# Utable_epaper_32seg_rev2.net
KiCad netlist of a schematic drawn in EAGLE
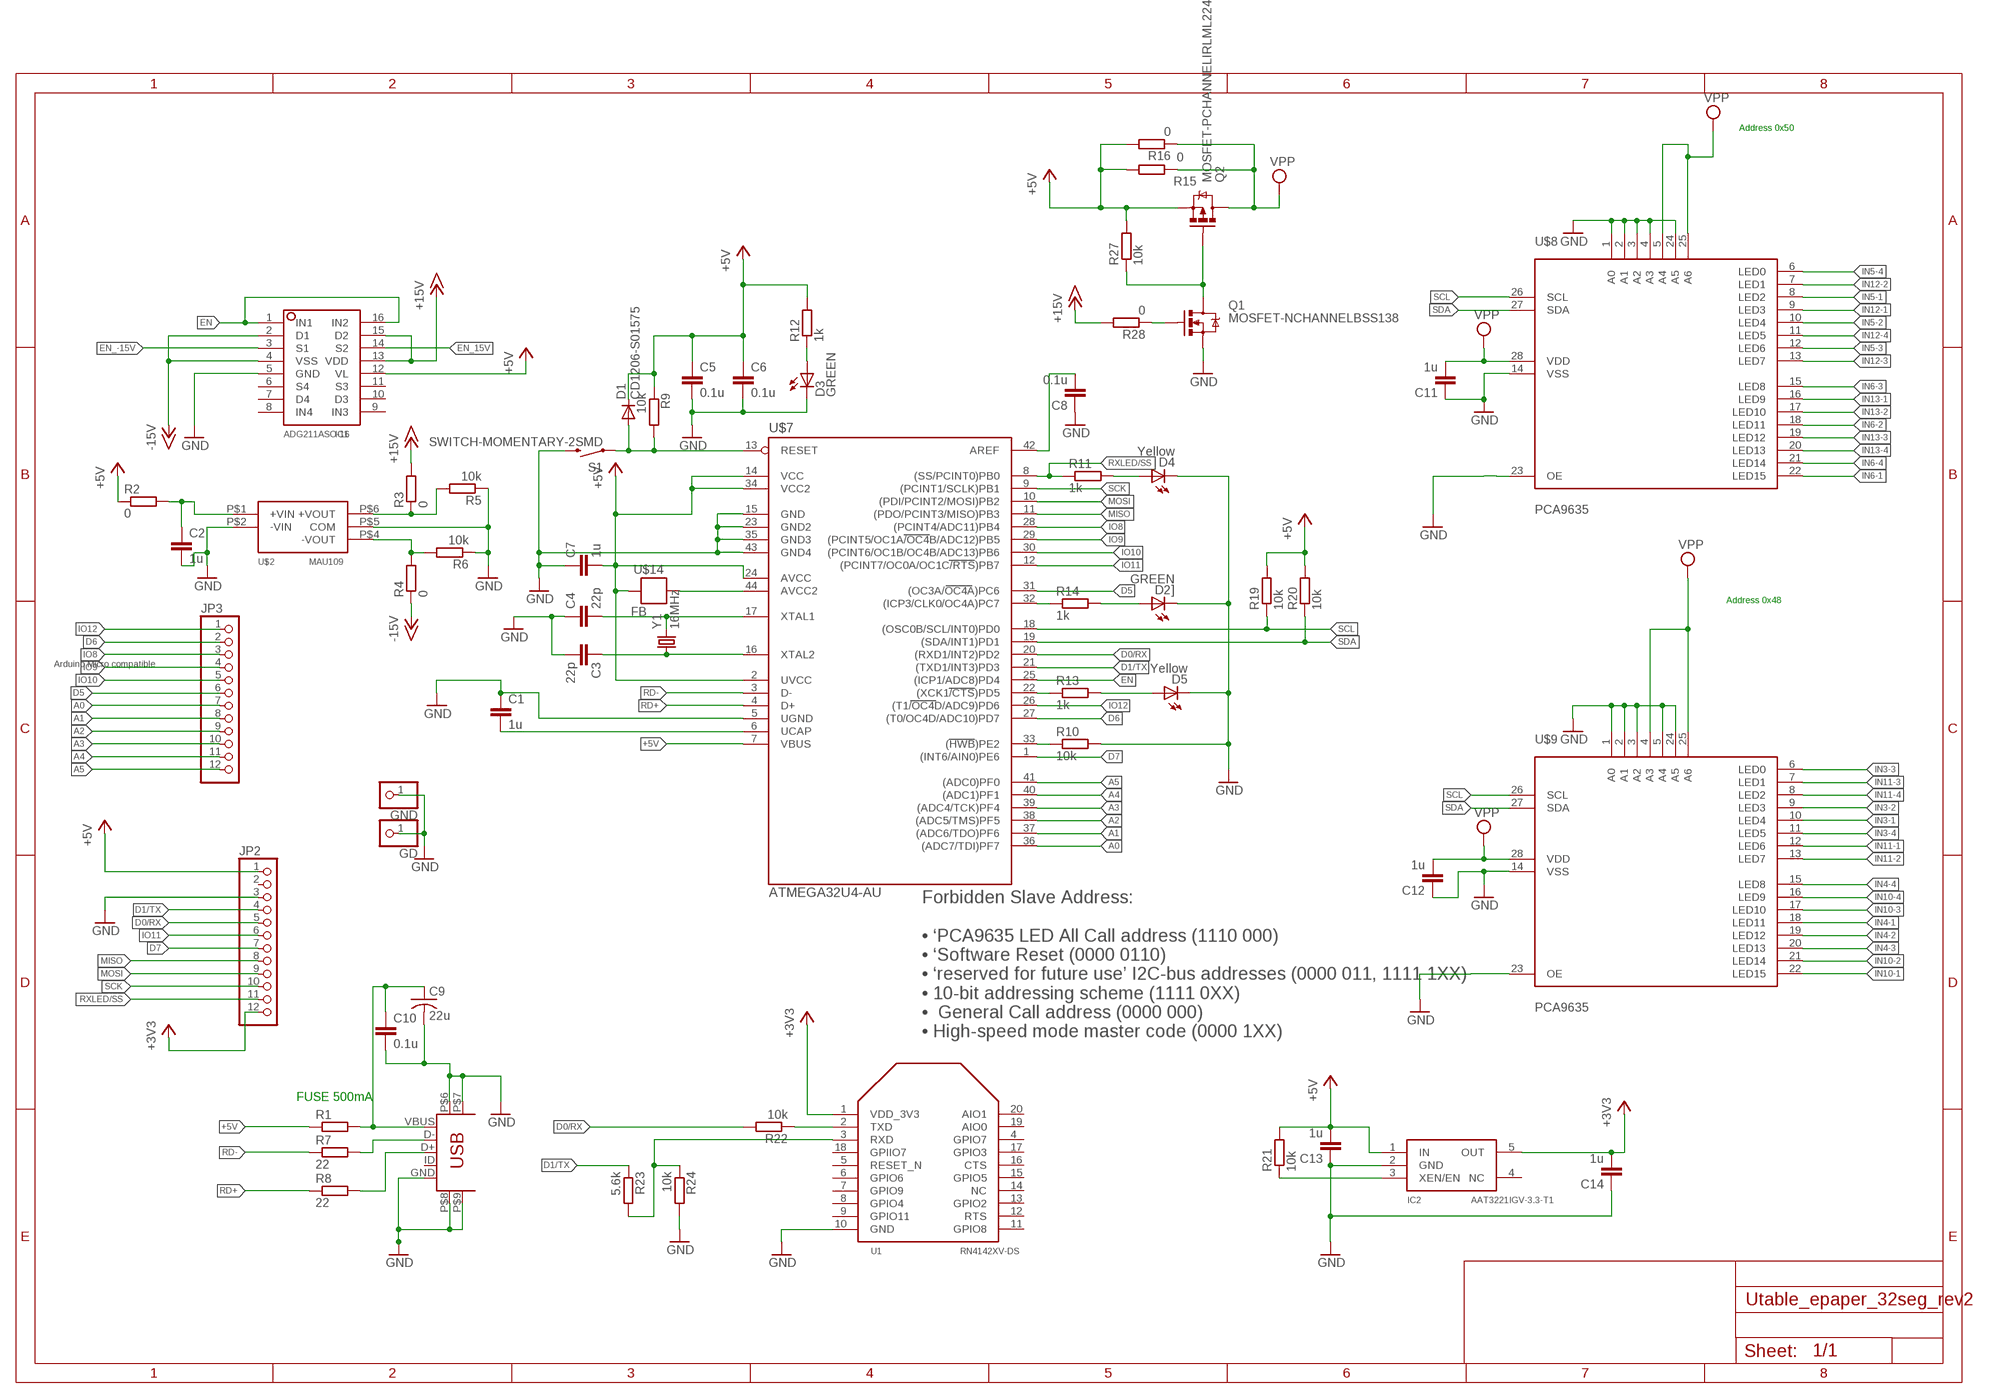
[diagram p0: schematic, sheet 1, part 1 of 2]
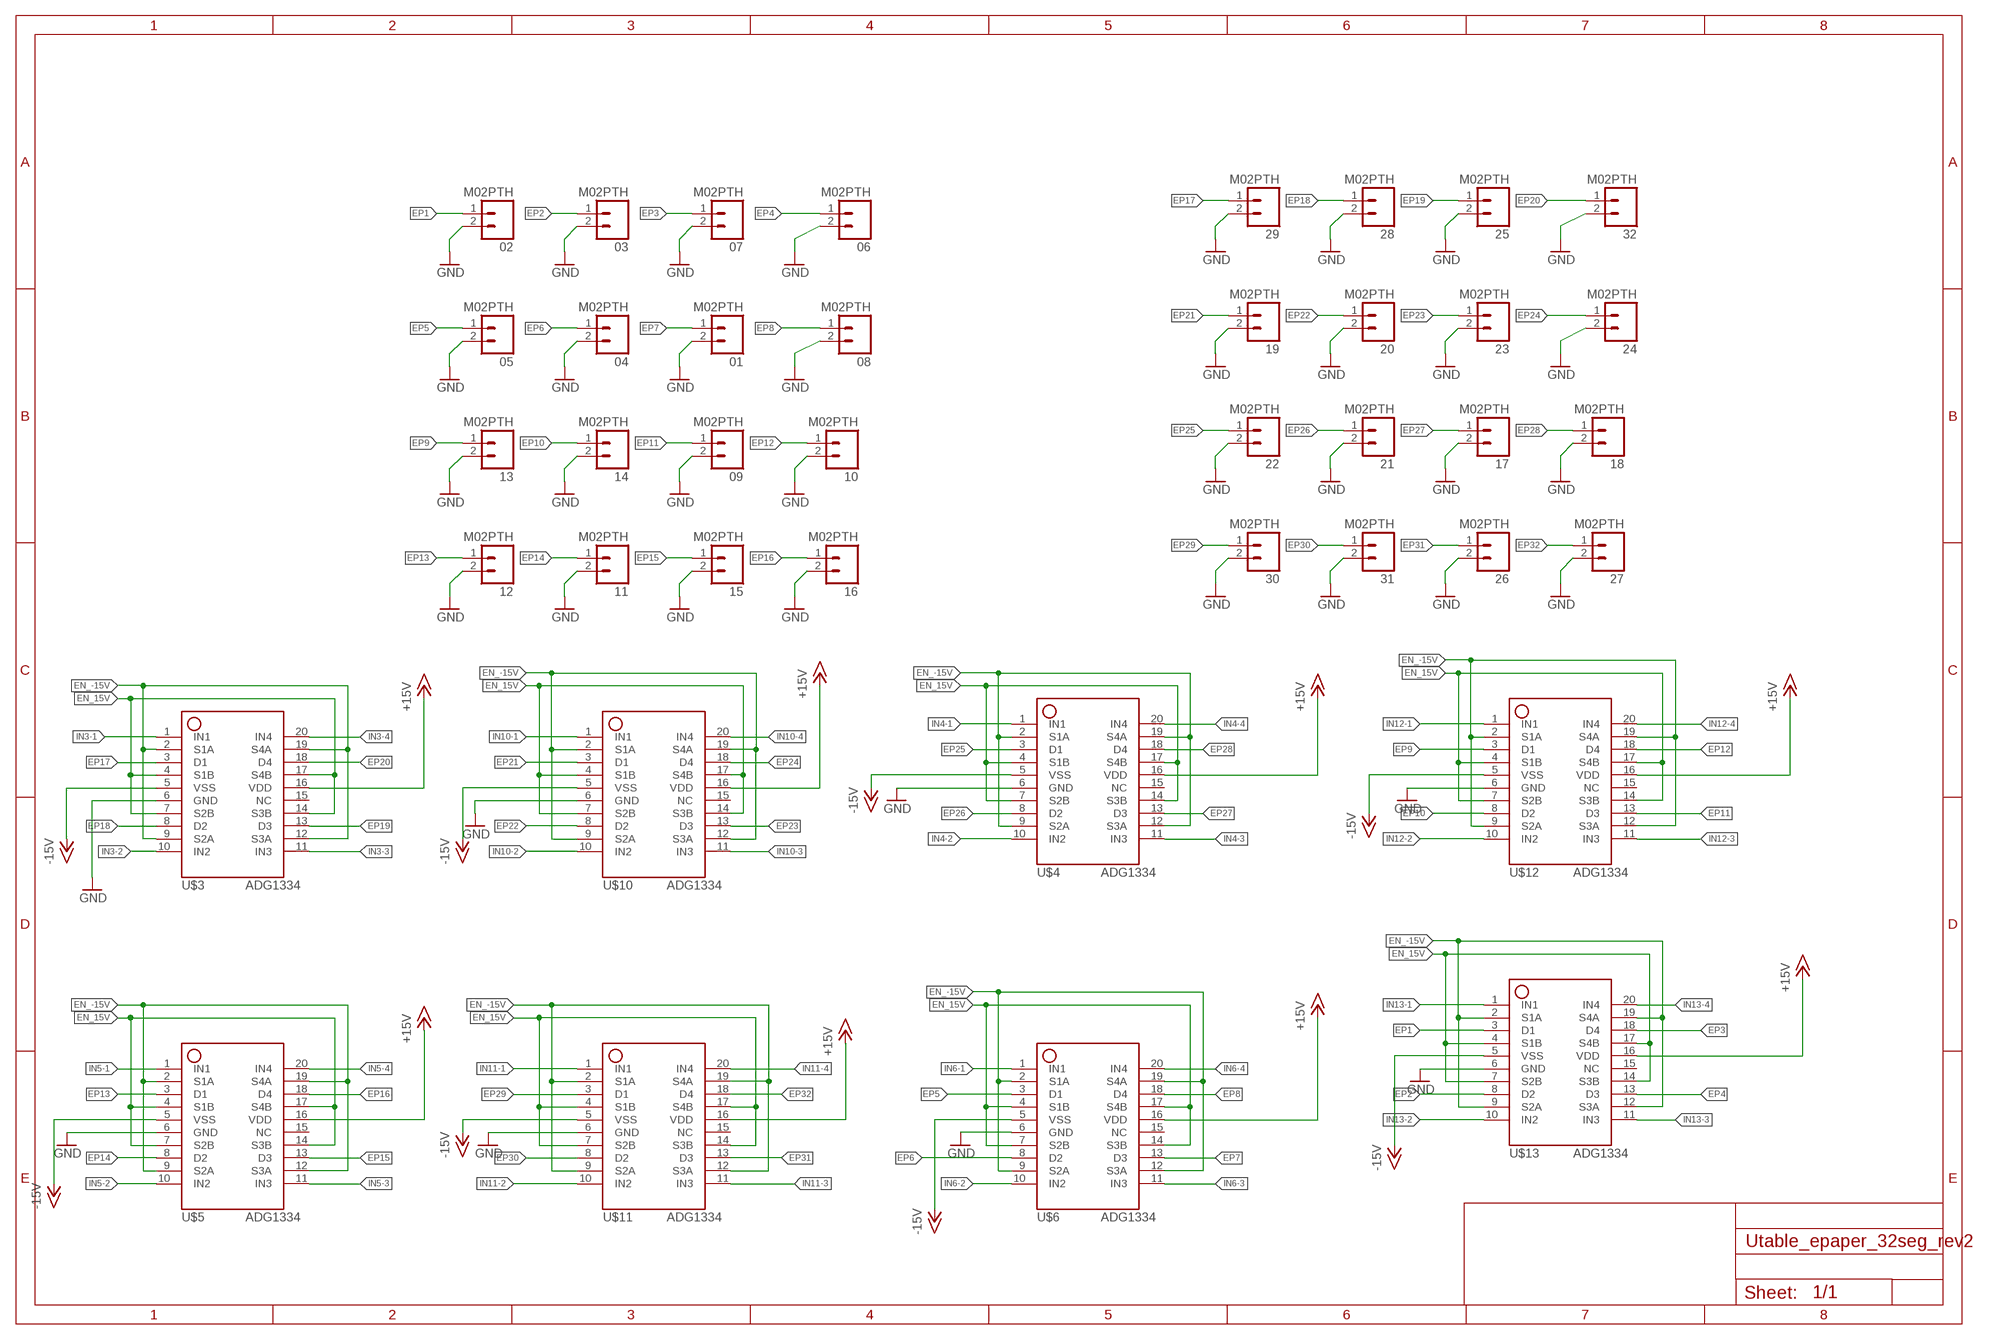
[diagram p1: schematic, sheet 1, part 2 of 2]

(export (version "E")
  (design (tool "Eeschema 10.0.6"))
  (components
    (comp (ref "01")
      (value "M02PTH")
      (footprint "eagle-import:1X02")
      (libsource (lib "eagle-import") (part "M02PTH"))
    )
    (comp (ref "02")
      (value "M02PTH")
      (footprint "eagle-import:1X02")
      (libsource (lib "eagle-import") (part "M02PTH"))
    )
    (comp (ref "03")
      (value "M02PTH")
      (footprint "eagle-import:1X02")
      (libsource (lib "eagle-import") (part "M02PTH"))
    )
    (comp (ref "04")
      (value "M02PTH")
      (footprint "eagle-import:1X02")
      (libsource (lib "eagle-import") (part "M02PTH"))
    )
    (comp (ref "05")
      (value "M02PTH")
      (footprint "eagle-import:1X02")
      (libsource (lib "eagle-import") (part "M02PTH"))
    )
    (comp (ref "06")
      (value "M02PTH")
      (footprint "eagle-import:1X02")
      (libsource (lib "eagle-import") (part "M02PTH"))
    )
    (comp (ref "07")
      (value "M02PTH")
      (footprint "eagle-import:1X02")
      (libsource (lib "eagle-import") (part "M02PTH"))
    )
    (comp (ref "08")
      (value "M02PTH")
      (footprint "eagle-import:1X02")
      (libsource (lib "eagle-import") (part "M02PTH"))
    )
    (comp (ref "09")
      (value "M02PTH")
      (footprint "eagle-import:1X02")
      (libsource (lib "eagle-import") (part "M02PTH"))
    )
    (comp (ref "10")
      (value "M02PTH")
      (footprint "eagle-import:1X02")
      (libsource (lib "eagle-import") (part "M02PTH"))
    )
    (comp (ref "11")
      (value "M02PTH")
      (footprint "eagle-import:1X02")
      (libsource (lib "eagle-import") (part "M02PTH"))
    )
    (comp (ref "12")
      (value "M02PTH")
      (footprint "eagle-import:1X02")
      (libsource (lib "eagle-import") (part "M02PTH"))
    )
    (comp (ref "13")
      (value "M02PTH")
      (footprint "eagle-import:1X02")
      (libsource (lib "eagle-import") (part "M02PTH"))
    )
    (comp (ref "14")
      (value "M02PTH")
      (footprint "eagle-import:1X02")
      (libsource (lib "eagle-import") (part "M02PTH"))
    )
    (comp (ref "15")
      (value "M02PTH")
      (footprint "eagle-import:1X02")
      (libsource (lib "eagle-import") (part "M02PTH"))
    )
    (comp (ref "16")
      (value "M02PTH")
      (footprint "eagle-import:1X02")
      (libsource (lib "eagle-import") (part "M02PTH"))
    )
    (comp (ref "17")
      (value "M02PTH")
      (footprint "eagle-import:1X02")
      (libsource (lib "eagle-import") (part "M02PTH"))
    )
    (comp (ref "18")
      (value "M02PTH")
      (footprint "eagle-import:1X02")
      (libsource (lib "eagle-import") (part "M02PTH"))
    )
    (comp (ref "19")
      (value "M02PTH")
      (footprint "eagle-import:1X02")
      (libsource (lib "eagle-import") (part "M02PTH"))
    )
    (comp (ref "20")
      (value "M02PTH")
      (footprint "eagle-import:1X02")
      (libsource (lib "eagle-import") (part "M02PTH"))
    )
    (comp (ref "21")
      (value "M02PTH")
      (footprint "eagle-import:1X02")
      (libsource (lib "eagle-import") (part "M02PTH"))
    )
    (comp (ref "22")
      (value "M02PTH")
      (footprint "eagle-import:1X02")
      (libsource (lib "eagle-import") (part "M02PTH"))
    )
    (comp (ref "23")
      (value "M02PTH")
      (footprint "eagle-import:1X02")
      (libsource (lib "eagle-import") (part "M02PTH"))
    )
    (comp (ref "24")
      (value "M02PTH")
      (footprint "eagle-import:1X02")
      (libsource (lib "eagle-import") (part "M02PTH"))
    )
    (comp (ref "25")
      (value "M02PTH")
      (footprint "eagle-import:1X02")
      (libsource (lib "eagle-import") (part "M02PTH"))
    )
    (comp (ref "26")
      (value "M02PTH")
      (footprint "eagle-import:1X02")
      (libsource (lib "eagle-import") (part "M02PTH"))
    )
    (comp (ref "27")
      (value "M02PTH")
      (footprint "eagle-import:1X02")
      (libsource (lib "eagle-import") (part "M02PTH"))
    )
    (comp (ref "28")
      (value "M02PTH")
      (footprint "eagle-import:1X02")
      (libsource (lib "eagle-import") (part "M02PTH"))
    )
    (comp (ref "29")
      (value "M02PTH")
      (footprint "eagle-import:1X02")
      (libsource (lib "eagle-import") (part "M02PTH"))
    )
    (comp (ref "30")
      (value "M02PTH")
      (footprint "eagle-import:1X02")
      (libsource (lib "eagle-import") (part "M02PTH"))
    )
    (comp (ref "31")
      (value "M02PTH")
      (footprint "eagle-import:1X02")
      (libsource (lib "eagle-import") (part "M02PTH"))
    )
    (comp (ref "32")
      (value "M02PTH")
      (footprint "eagle-import:1X02")
      (libsource (lib "eagle-import") (part "M02PTH"))
    )
    (comp (ref "C1")
      (value "1u")
      (footprint "eagle-import:C0603K")
      (libsource (lib "eagle-import") (part "C-EUC0603K"))
    )
    (comp (ref "C2")
      (value "1u")
      (footprint "eagle-import:C0603")
      (libsource (lib "eagle-import") (part "C-EUC0603"))
    )
    (comp (ref "C3")
      (value "22p")
      (footprint "eagle-import:C0603K")
      (libsource (lib "eagle-import") (part "C-EUC0603K"))
    )
    (comp (ref "C4")
      (value "22p")
      (footprint "eagle-import:C0603K")
      (libsource (lib "eagle-import") (part "C-EUC0603K"))
    )
    (comp (ref "C5")
      (value "0.1u")
      (footprint "eagle-import:C0603K")
      (libsource (lib "eagle-import") (part "C-EUC0603K"))
    )
    (comp (ref "C6")
      (value "0.1u")
      (footprint "eagle-import:C0603K")
      (libsource (lib "eagle-import") (part "C-EUC0603K"))
    )
    (comp (ref "C7")
      (value "1u")
      (footprint "eagle-import:C0603K")
      (libsource (lib "eagle-import") (part "C-EUC0603K"))
    )
    (comp (ref "C8")
      (value "0.1u")
      (footprint "eagle-import:C0603K")
      (libsource (lib "eagle-import") (part "C-EUC0603K"))
    )
    (comp (ref "C9")
      (value "22u")
      (footprint "eagle-import:C0805K")
      (libsource (lib "eagle-import") (part "C-USC0805K"))
    )
    (comp (ref "C10")
      (value "0.1u")
      (footprint "eagle-import:C0603K")
      (libsource (lib "eagle-import") (part "C-EUC0603K"))
    )
    (comp (ref "C11")
      (value "1u")
      (footprint "eagle-import:C0603K")
      (libsource (lib "eagle-import") (part "C-EUC0603K"))
    )
    (comp (ref "C12")
      (value "1u")
      (footprint "eagle-import:C0603K")
      (libsource (lib "eagle-import") (part "C-EUC0603K"))
    )
    (comp (ref "C13")
      (value "1u")
      (footprint "eagle-import:C0603K")
      (libsource (lib "eagle-import") (part "C-EUC0603K"))
    )
    (comp (ref "C14")
      (value "1u")
      (footprint "eagle-import:C0603K")
      (libsource (lib "eagle-import") (part "C-EUC0603K"))
    )
    (comp (ref "D1")
      (value "CD1206-S01575")
      (footprint "eagle-import:1206")
      (libsource (lib "eagle-import") (part "CD1206-S01575"))
    )
    (comp (ref "D2]")
      (value "GREEN")
      (footprint "eagle-import:LED-0603")
      (libsource (lib "eagle-import") (part "LED-GREEN0603"))
    )
    (comp (ref "D3")
      (value "GREEN")
      (footprint "eagle-import:LED-0603")
      (libsource (lib "eagle-import") (part "LED-GREEN0603"))
    )
    (comp (ref "D4")
      (value "Yellow")
      (footprint "eagle-import:LED-0603")
      (libsource (lib "eagle-import") (part "LED-YELLOW0603"))
    )
    (comp (ref "D5")
      (value "Yellow")
      (footprint "eagle-import:LED-0603")
      (libsource (lib "eagle-import") (part "LED-YELLOW0603"))
    )
    (comp (ref "GD")
      (value "PINHD-1X1")
      (footprint "eagle-import:1X01")
      (libsource (lib "eagle-import") (part "PINHD-1X1"))
    )
    (comp (ref "GND")
      (value "PINHD-1X1")
      (footprint "eagle-import:1X01")
      (libsource (lib "eagle-import") (part "PINHD-1X1"))
    )
    (comp (ref "IC1")
      (value "ADG211ASO-16")
      (footprint "eagle-import:SO-16")
      (libsource (lib "eagle-import") (part "ADG211ASO-16"))
    )
    (comp (ref "IC2")
      (value "AAT3221IGV-3.3-T1")
      (footprint "eagle-import:SOT23-5")
      (libsource (lib "eagle-import") (part "AAT3221IGV-3.3-T1"))
    )
    (comp (ref "JP2")
      (value "PINHD-1X12")
      (footprint "eagle-import:1X12")
      (libsource (lib "eagle-import") (part "PINHD-1X12"))
    )
    (comp (ref "JP3")
      (value "PINHD-1X12")
      (footprint "eagle-import:1X12")
      (libsource (lib "eagle-import") (part "PINHD-1X12"))
    )
    (comp (ref "Q1")
      (value "MOSFET-NCHANNELBSS138")
      (footprint "eagle-import:SOT23")
      (libsource (lib "eagle-import") (part "MOSFET-NCHANNELBSS138"))
    )
    (comp (ref "Q2")
      (value "MOSFET-PCHANNELIRLML2244")
      (footprint "eagle-import:SOT23-3")
      (libsource (lib "eagle-import") (part "MOSFET-PCHANNELIRLML2244"))
    )
    (comp (ref "R1")
      (value "R-EU_R0603")
      (footprint "eagle-import:R0603")
      (libsource (lib "eagle-import") (part "R-EU_R0603"))
    )
    (comp (ref "R2")
      (value "0")
      (footprint "eagle-import:R0603")
      (libsource (lib "eagle-import") (part "R-EU_R0603"))
    )
    (comp (ref "R3")
      (value "0")
      (footprint "eagle-import:R0603")
      (libsource (lib "eagle-import") (part "R-EU_R0603"))
    )
    (comp (ref "R4")
      (value "0")
      (footprint "eagle-import:R0603")
      (libsource (lib "eagle-import") (part "R-EU_R0603"))
    )
    (comp (ref "R5")
      (value "10k")
      (footprint "eagle-import:R0603")
      (libsource (lib "eagle-import") (part "R-EU_R0603"))
    )
    (comp (ref "R6")
      (value "10k")
      (footprint "eagle-import:R0603")
      (libsource (lib "eagle-import") (part "R-EU_R0603"))
    )
    (comp (ref "R7")
      (value "22")
      (footprint "eagle-import:R0603")
      (libsource (lib "eagle-import") (part "R-EU_R0603"))
    )
    (comp (ref "R8")
      (value "22")
      (footprint "eagle-import:R0603")
      (libsource (lib "eagle-import") (part "R-EU_R0603"))
    )
    (comp (ref "R9")
      (value "10k")
      (footprint "eagle-import:R0603")
      (libsource (lib "eagle-import") (part "R-EU_R0603"))
    )
    (comp (ref "R10")
      (value "10k")
      (footprint "eagle-import:R0603")
      (libsource (lib "eagle-import") (part "R-EU_R0603"))
    )
    (comp (ref "R11")
      (value "1k")
      (footprint "eagle-import:R0603")
      (libsource (lib "eagle-import") (part "R-EU_R0603"))
    )
    (comp (ref "R12")
      (value "1k")
      (footprint "eagle-import:R0603")
      (libsource (lib "eagle-import") (part "R-EU_R0603"))
    )
    (comp (ref "R13")
      (value "1k")
      (footprint "eagle-import:R0603")
      (libsource (lib "eagle-import") (part "R-EU_R0603"))
    )
    (comp (ref "R14")
      (value "1k")
      (footprint "eagle-import:R0603")
      (libsource (lib "eagle-import") (part "R-EU_R0603"))
    )
    (comp (ref "R15")
      (value "0")
      (footprint "eagle-import:R0603")
      (libsource (lib "eagle-import") (part "R-EU_R0603"))
    )
    (comp (ref "R16")
      (value "0")
      (footprint "eagle-import:R0603")
      (libsource (lib "eagle-import") (part "R-EU_R0603"))
    )
    (comp (ref "R19")
      (value "10k")
      (footprint "eagle-import:R0603")
      (libsource (lib "eagle-import") (part "R-EU_R0603"))
    )
    (comp (ref "R20")
      (value "10k")
      (footprint "eagle-import:R0603")
      (libsource (lib "eagle-import") (part "R-EU_R0603"))
    )
    (comp (ref "R21")
      (value "10k")
      (footprint "eagle-import:R0603")
      (libsource (lib "eagle-import") (part "R-EU_R0603"))
    )
    (comp (ref "R22")
      (value "10k")
      (footprint "eagle-import:R0603")
      (libsource (lib "eagle-import") (part "R-EU_R0603"))
    )
    (comp (ref "R23")
      (value "5.6k")
      (footprint "eagle-import:R0603")
      (libsource (lib "eagle-import") (part "R-EU_R0603"))
    )
    (comp (ref "R24")
      (value "10k")
      (footprint "eagle-import:R0603")
      (libsource (lib "eagle-import") (part "R-EU_R0603"))
    )
    (comp (ref "R27")
      (value "10k")
      (footprint "eagle-import:R0603")
      (libsource (lib "eagle-import") (part "R-EU_R0603"))
    )
    (comp (ref "R28")
      (value "0")
      (footprint "eagle-import:R0603")
      (libsource (lib "eagle-import") (part "R-EU_R0603"))
    )
    (comp (ref "S1")
      (value "SWITCH-MOMENTARY-2SMD")
      (footprint "eagle-import:TACTILE-SWITCH-SMD")
      (libsource (lib "eagle-import") (part "SWITCH-MOMENTARY-2SMD"))
    )
    (comp (ref "U$1")
      (value "USB_MICRO_FCI")
      (footprint "eagle-import:USB_MICRO_FCI")
      (libsource (lib "eagle-import") (part "USB_MICRO_FCI"))
    )
    (comp (ref "U$2")
      (value "MAU109")
      (footprint "eagle-import:MAU109")
      (libsource (lib "eagle-import") (part "MAU109"))
    )
    (comp (ref "U$3")
      (value "ADG1334")
      (footprint "eagle-import:SSOP20")
      (libsource (lib "eagle-import") (part "ADG1334"))
    )
    (comp (ref "U$4")
      (value "ADG1334")
      (footprint "eagle-import:SSOP20")
      (libsource (lib "eagle-import") (part "ADG1334"))
    )
    (comp (ref "U$5")
      (value "ADG1334")
      (footprint "eagle-import:SSOP20")
      (libsource (lib "eagle-import") (part "ADG1334"))
    )
    (comp (ref "U$6")
      (value "ADG1334")
      (footprint "eagle-import:SSOP20")
      (libsource (lib "eagle-import") (part "ADG1334"))
    )
    (comp (ref "U$7")
      (value "ATMEGA32U4-AU")
      (footprint "eagle-import:TQFP44")
      (libsource (lib "eagle-import") (part "ATMEGA32U4-AU"))
    )
    (comp (ref "U$8")
      (value "PCA9635")
      (footprint "eagle-import:PCA9635")
      (libsource (lib "eagle-import") (part "PCA9635"))
    )
    (comp (ref "U$9")
      (value "PCA9635")
      (footprint "eagle-import:PCA9635")
      (libsource (lib "eagle-import") (part "PCA9635"))
    )
    (comp (ref "U$10")
      (value "ADG1334")
      (footprint "eagle-import:SSOP20")
      (libsource (lib "eagle-import") (part "ADG1334"))
    )
    (comp (ref "U$11")
      (value "ADG1334")
      (footprint "eagle-import:SSOP20")
      (libsource (lib "eagle-import") (part "ADG1334"))
    )
    (comp (ref "U$12")
      (value "ADG1334")
      (footprint "eagle-import:SSOP20")
      (libsource (lib "eagle-import") (part "ADG1334"))
    )
    (comp (ref "U$13")
      (value "ADG1334")
      (footprint "eagle-import:SSOP20")
      (libsource (lib "eagle-import") (part "ADG1334"))
    )
    (comp (ref "U$14")
      (value "FB")
      (footprint "eagle-import:0603")
      (libsource (lib "eagle-import") (part "FB"))
    )
    (comp (ref "U1")
      (value "RN4142XV-DS")
      (footprint "eagle-import:XBEE")
      (libsource (lib "eagle-import") (part "RN4142XV-DS"))
    )
    (comp (ref "Y1")
      (value "16MHz")
      (footprint "eagle-import:OSCILLATOR-3225")
      (libsource (lib "eagle-import") (part "403C11E16M00000"))
    )
  )
  (nets
    (net (code "1") (name "+3V3") (class "Default")
      (node (ref "C14") (pin "2") (pinfunction "2_2") (pintype "passive"))
      (node (ref "IC2") (pin "5") (pinfunction "OUT_5") (pintype "bidirectional"))
      (node (ref "JP2") (pin "12") (pinfunction "12_12") (pintype "passive"))
      (node (ref "U1") (pin "1") (pinfunction "VDD_3V3_1") (pintype "power_in"))
    )
    (net (code "2") (name "+5V") (class "Default")
      (node (ref "C13") (pin "2") (pinfunction "2_2") (pintype "passive"))
      (node (ref "C5") (pin "1") (pinfunction "1_1") (pintype "passive"))
      (node (ref "C6") (pin "1") (pinfunction "1_1") (pintype "passive"))
      (node (ref "C7") (pin "2") (pinfunction "2_2") (pintype "passive"))
      (node (ref "D1") (pin "2") (pinfunction "C_2") (pintype "passive"))
      (node (ref "IC1") (pin "12") (pinfunction "VL_12") (pintype "bidirectional"))
      (node (ref "IC2") (pin "1") (pinfunction "IN_1") (pintype "bidirectional"))
      (node (ref "JP2") (pin "1") (pinfunction "1_1") (pintype "passive"))
      (node (ref "Q2") (pin "2") (pinfunction "S_2") (pintype "passive"))
      (node (ref "R1") (pin "1") (pinfunction "1_1") (pintype "passive"))
      (node (ref "R12") (pin "2") (pinfunction "2_2") (pintype "passive"))
      (node (ref "R15") (pin "2") (pinfunction "2_2") (pintype "passive"))
      (node (ref "R16") (pin "2") (pinfunction "2_2") (pintype "passive"))
      (node (ref "R19") (pin "2") (pinfunction "2_2") (pintype "passive"))
      (node (ref "R2") (pin "1") (pinfunction "1_1") (pintype "passive"))
      (node (ref "R20") (pin "2") (pinfunction "2_2") (pintype "passive"))
      (node (ref "R21") (pin "2") (pinfunction "2_2") (pintype "passive"))
      (node (ref "R27") (pin "2") (pinfunction "2_2") (pintype "passive"))
      (node (ref "R9") (pin "1") (pinfunction "1_1") (pintype "passive"))
      (node (ref "U$14") (pin "2") (pinfunction "P$2_2") (pintype "bidirectional"))
      (node (ref "U$7") (pin "14") (pinfunction "VCC_14") (pintype "bidirectional"))
      (node (ref "U$7") (pin "2") (pinfunction "UVCC_2") (pintype "bidirectional"))
      (node (ref "U$7") (pin "24") (pinfunction "AVCC_24") (pintype "bidirectional"))
      (node (ref "U$7") (pin "34") (pinfunction "VCC2_34") (pintype "bidirectional"))
      (node (ref "U$7") (pin "7") (pinfunction "VBUS_7") (pintype "bidirectional"))
    )
    (net (code "3") (name "+15V") (class "Default")
      (node (ref "IC1") (pin "13") (pinfunction "VDD_13") (pintype "bidirectional"))
      (node (ref "IC1") (pin "15") (pinfunction "D2_15") (pintype "bidirectional"))
      (node (ref "R28") (pin "2") (pinfunction "2_2") (pintype "passive"))
      (node (ref "R3") (pin "2") (pinfunction "2_2") (pintype "passive"))
      (node (ref "U$10") (pin "16") (pinfunction "VDD_16") (pintype "bidirectional"))
      (node (ref "U$11") (pin "16") (pinfunction "VDD_16") (pintype "bidirectional"))
      (node (ref "U$12") (pin "16") (pinfunction "VDD_16") (pintype "bidirectional"))
      (node (ref "U$13") (pin "16") (pinfunction "VDD_16") (pintype "bidirectional"))
      (node (ref "U$3") (pin "16") (pinfunction "VDD_16") (pintype "bidirectional"))
      (node (ref "U$4") (pin "16") (pinfunction "VDD_16") (pintype "bidirectional"))
      (node (ref "U$5") (pin "16") (pinfunction "VDD_16") (pintype "bidirectional"))
      (node (ref "U$6") (pin "16") (pinfunction "VDD_16") (pintype "bidirectional"))
    )
    (net (code "4") (name "-15V") (class "Default")
      (node (ref "IC1") (pin "2") (pinfunction "D1_2") (pintype "bidirectional"))
      (node (ref "IC1") (pin "4") (pinfunction "VSS_4") (pintype "bidirectional"))
      (node (ref "R4") (pin "1") (pinfunction "1_1") (pintype "passive"))
      (node (ref "U$10") (pin "5") (pinfunction "VSS_5") (pintype "bidirectional"))
      (node (ref "U$11") (pin "5") (pinfunction "VSS_5") (pintype "bidirectional"))
      (node (ref "U$12") (pin "5") (pinfunction "VSS_5") (pintype "bidirectional"))
      (node (ref "U$13") (pin "5") (pinfunction "VSS_5") (pintype "bidirectional"))
      (node (ref "U$3") (pin "5") (pinfunction "VSS_5") (pintype "bidirectional"))
      (node (ref "U$4") (pin "5") (pinfunction "VSS_5") (pintype "bidirectional"))
      (node (ref "U$5") (pin "5") (pinfunction "VSS_5") (pintype "bidirectional"))
      (node (ref "U$6") (pin "5") (pinfunction "VSS_5") (pintype "bidirectional"))
    )
    (net (code "5") (name "A0") (class "Default")
      (node (ref "JP3") (pin "7") (pinfunction "7_7") (pintype "passive"))
      (node (ref "U$7") (pin "36") (pinfunction "(ADC7/TDI)PF7_36") (pintype "bidirectional"))
    )
    (net (code "6") (name "A1") (class "Default")
      (node (ref "JP3") (pin "8") (pinfunction "8_8") (pintype "passive"))
      (node (ref "U$7") (pin "37") (pinfunction "(ADC6/TDO)PF6_37") (pintype "bidirectional"))
    )
    (net (code "7") (name "A2") (class "Default")
      (node (ref "JP3") (pin "9") (pinfunction "9_9") (pintype "passive"))
      (node (ref "U$7") (pin "38") (pinfunction "(ADC5/TMS)PF5_38") (pintype "bidirectional"))
    )
    (net (code "8") (name "A3") (class "Default")
      (node (ref "JP3") (pin "10") (pinfunction "10_10") (pintype "passive"))
      (node (ref "U$7") (pin "39") (pinfunction "(ADC4/TCK)PF4_39") (pintype "bidirectional"))
    )
    (net (code "9") (name "A4") (class "Default")
      (node (ref "JP3") (pin "11") (pinfunction "11_11") (pintype "passive"))
      (node (ref "U$7") (pin "40") (pinfunction "(ADC1)PF1_40") (pintype "bidirectional"))
    )
    (net (code "10") (name "A5") (class "Default")
      (node (ref "JP3") (pin "12") (pinfunction "12_12") (pintype "passive"))
      (node (ref "U$7") (pin "41") (pinfunction "(ADC0)PF0_41") (pintype "bidirectional"))
    )
    (net (code "11") (name "D0{slash}RX") (class "Default")
      (node (ref "JP2") (pin "5") (pinfunction "5_5") (pintype "passive"))
      (node (ref "R22") (pin "2") (pinfunction "2_2") (pintype "passive"))
      (node (ref "U$7") (pin "20") (pinfunction "(RXD1/INT2)PD2_20") (pintype "bidirectional"))
    )
    (net (code "12") (name "D1{slash}TX") (class "Default")
      (node (ref "JP2") (pin "4") (pinfunction "4_4") (pintype "passive"))
      (node (ref "R23") (pin "1") (pinfunction "1_1") (pintype "passive"))
      (node (ref "U$7") (pin "21") (pinfunction "(TXD1/INT3)PD3_21") (pintype "bidirectional"))
    )
    (net (code "13") (name "D5") (class "Default")
      (node (ref "JP3") (pin "6") (pinfunction "6_6") (pintype "passive"))
      (node (ref "U$7") (pin "31") (pinfunction "(OC3A/OC4A)PC6_31") (pintype "bidirectional"))
    )
    (net (code "14") (name "D6") (class "Default")
      (node (ref "JP3") (pin "2") (pinfunction "2_2") (pintype "passive"))
      (node (ref "U$7") (pin "27") (pinfunction "(T0/OC4D/ADC10)PD7_27") (pintype "bidirectional"))
    )
    (net (code "15") (name "D7") (class "Default")
      (node (ref "JP2") (pin "7") (pinfunction "7_7") (pintype "passive"))
      (node (ref "U$7") (pin "1") (pinfunction "(INT6/AIN0)PE6_1") (pintype "bidirectional"))
    )
    (net (code "16") (name "EN") (class "Default")
      (node (ref "IC1") (pin "1") (pinfunction "IN1_1") (pintype "input"))
      (node (ref "IC1") (pin "16") (pinfunction "IN2_16") (pintype "bidirectional"))
      (node (ref "U$7") (pin "25") (pinfunction "(ICP1/ADC8)PD4_25") (pintype "bidirectional"))
    )
    (net (code "17") (name "EN_-15V") (class "Default")
      (node (ref "IC1") (pin "3") (pinfunction "S1_3") (pintype "bidirectional"))
      (node (ref "U$10") (pin "12") (pinfunction "S3A_12") (pintype "bidirectional"))
      (node (ref "U$10") (pin "19") (pinfunction "S4A_19") (pintype "bidirectional"))
      (node (ref "U$10") (pin "2") (pinfunction "S1A_2") (pintype "bidirectional"))
      (node (ref "U$10") (pin "9") (pinfunction "S2A_9") (pintype "bidirectional"))
      (node (ref "U$11") (pin "12") (pinfunction "S3A_12") (pintype "bidirectional"))
      (node (ref "U$11") (pin "19") (pinfunction "S4A_19") (pintype "bidirectional"))
      (node (ref "U$11") (pin "2") (pinfunction "S1A_2") (pintype "bidirectional"))
      (node (ref "U$11") (pin "9") (pinfunction "S2A_9") (pintype "bidirectional"))
      (node (ref "U$12") (pin "12") (pinfunction "S3A_12") (pintype "bidirectional"))
      (node (ref "U$12") (pin "19") (pinfunction "S4A_19") (pintype "bidirectional"))
      (node (ref "U$12") (pin "2") (pinfunction "S1A_2") (pintype "bidirectional"))
      (node (ref "U$12") (pin "9") (pinfunction "S2A_9") (pintype "bidirectional"))
      (node (ref "U$13") (pin "12") (pinfunction "S3A_12") (pintype "bidirectional"))
      (node (ref "U$13") (pin "19") (pinfunction "S4A_19") (pintype "bidirectional"))
      (node (ref "U$13") (pin "2") (pinfunction "S1A_2") (pintype "bidirectional"))
      (node (ref "U$13") (pin "9") (pinfunction "S2A_9") (pintype "bidirectional"))
      (node (ref "U$3") (pin "12") (pinfunction "S3A_12") (pintype "bidirectional"))
      (node (ref "U$3") (pin "19") (pinfunction "S4A_19") (pintype "bidirectional"))
      (node (ref "U$3") (pin "2") (pinfunction "S1A_2") (pintype "bidirectional"))
      (node (ref "U$3") (pin "9") (pinfunction "S2A_9") (pintype "bidirectional"))
      (node (ref "U$4") (pin "12") (pinfunction "S3A_12") (pintype "bidirectional"))
      (node (ref "U$4") (pin "19") (pinfunction "S4A_19") (pintype "bidirectional"))
      (node (ref "U$4") (pin "2") (pinfunction "S1A_2") (pintype "bidirectional"))
      (node (ref "U$4") (pin "9") (pinfunction "S2A_9") (pintype "bidirectional"))
      (node (ref "U$5") (pin "12") (pinfunction "S3A_12") (pintype "bidirectional"))
      (node (ref "U$5") (pin "19") (pinfunction "S4A_19") (pintype "bidirectional"))
      (node (ref "U$5") (pin "2") (pinfunction "S1A_2") (pintype "bidirectional"))
      (node (ref "U$5") (pin "9") (pinfunction "S2A_9") (pintype "bidirectional"))
      (node (ref "U$6") (pin "12") (pinfunction "S3A_12") (pintype "bidirectional"))
      (node (ref "U$6") (pin "19") (pinfunction "S4A_19") (pintype "bidirectional"))
      (node (ref "U$6") (pin "2") (pinfunction "S1A_2") (pintype "bidirectional"))
      (node (ref "U$6") (pin "9") (pinfunction "S2A_9") (pintype "bidirectional"))
    )
    (net (code "18") (name "EN_15V") (class "Default")
      (node (ref "IC1") (pin "14") (pinfunction "S2_14") (pintype "bidirectional"))
      (node (ref "U$10") (pin "14") (pinfunction "S3B_14") (pintype "bidirectional"))
      (node (ref "U$10") (pin "17") (pinfunction "S4B_17") (pintype "bidirectional"))
      (node (ref "U$10") (pin "4") (pinfunction "S1B_4") (pintype "bidirectional"))
      (node (ref "U$10") (pin "7") (pinfunction "S2B_7") (pintype "bidirectional"))
      (node (ref "U$11") (pin "14") (pinfunction "S3B_14") (pintype "bidirectional"))
      (node (ref "U$11") (pin "17") (pinfunction "S4B_17") (pintype "bidirectional"))
      (node (ref "U$11") (pin "4") (pinfunction "S1B_4") (pintype "bidirectional"))
      (node (ref "U$11") (pin "7") (pinfunction "S2B_7") (pintype "bidirectional"))
      (node (ref "U$12") (pin "14") (pinfunction "S3B_14") (pintype "bidirectional"))
      (node (ref "U$12") (pin "17") (pinfunction "S4B_17") (pintype "bidirectional"))
      (node (ref "U$12") (pin "4") (pinfunction "S1B_4") (pintype "bidirectional"))
      (node (ref "U$12") (pin "7") (pinfunction "S2B_7") (pintype "bidirectional"))
      (node (ref "U$13") (pin "14") (pinfunction "S3B_14") (pintype "bidirectional"))
      (node (ref "U$13") (pin "17") (pinfunction "S4B_17") (pintype "bidirectional"))
      (node (ref "U$13") (pin "4") (pinfunction "S1B_4") (pintype "bidirectional"))
      (node (ref "U$13") (pin "7") (pinfunction "S2B_7") (pintype "bidirectional"))
      (node (ref "U$3") (pin "14") (pinfunction "S3B_14") (pintype "bidirectional"))
      (node (ref "U$3") (pin "17") (pinfunction "S4B_17") (pintype "bidirectional"))
      (node (ref "U$3") (pin "4") (pinfunction "S1B_4") (pintype "bidirectional"))
      (node (ref "U$3") (pin "7") (pinfunction "S2B_7") (pintype "bidirectional"))
      (node (ref "U$4") (pin "14") (pinfunction "S3B_14") (pintype "bidirectional"))
      (node (ref "U$4") (pin "17") (pinfunction "S4B_17") (pintype "bidirectional"))
      (node (ref "U$4") (pin "4") (pinfunction "S1B_4") (pintype "bidirectional"))
      (node (ref "U$4") (pin "7") (pinfunction "S2B_7") (pintype "bidirectional"))
      (node (ref "U$5") (pin "14") (pinfunction "S3B_14") (pintype "bidirectional"))
      (node (ref "U$5") (pin "17") (pinfunction "S4B_17") (pintype "bidirectional"))
      (node (ref "U$5") (pin "4") (pinfunction "S1B_4") (pintype "bidirectional"))
      (node (ref "U$5") (pin "7") (pinfunction "S2B_7") (pintype "bidirectional"))
      (node (ref "U$6") (pin "14") (pinfunction "S3B_14") (pintype "bidirectional"))
      (node (ref "U$6") (pin "17") (pinfunction "S4B_17") (pintype "bidirectional"))
      (node (ref "U$6") (pin "4") (pinfunction "S1B_4") (pintype "bidirectional"))
      (node (ref "U$6") (pin "7") (pinfunction "S2B_7") (pintype "bidirectional"))
    )
    (net (code "19") (name "EP1") (class "Default")
      (node (ref "02") (pin "1") (pinfunction "1_1") (pintype "passive"))
      (node (ref "U$13") (pin "3") (pinfunction "D1_3") (pintype "bidirectional"))
    )
    (net (code "20") (name "EP2") (class "Default")
      (node (ref "03") (pin "1") (pinfunction "1_1") (pintype "passive"))
      (node (ref "U$13") (pin "8") (pinfunction "D2_8") (pintype "bidirectional"))
    )
    (net (code "21") (name "EP3") (class "Default")
      (node (ref "07") (pin "1") (pinfunction "1_1") (pintype "passive"))
      (node (ref "U$13") (pin "18") (pinfunction "D4_18") (pintype "bidirectional"))
    )
    (net (code "22") (name "EP4") (class "Default")
      (node (ref "06") (pin "1") (pinfunction "1_1") (pintype "passive"))
      (node (ref "U$13") (pin "13") (pinfunction "D3_13") (pintype "bidirectional"))
    )
    (net (code "23") (name "EP5") (class "Default")
      (node (ref "05") (pin "1") (pinfunction "1_1") (pintype "passive"))
      (node (ref "U$6") (pin "3") (pinfunction "D1_3") (pintype "bidirectional"))
    )
    (net (code "24") (name "EP6") (class "Default")
      (node (ref "04") (pin "1") (pinfunction "1_1") (pintype "passive"))
      (node (ref "U$6") (pin "8") (pinfunction "D2_8") (pintype "bidirectional"))
    )
    (net (code "25") (name "EP7") (class "Default")
      (node (ref "01") (pin "1") (pinfunction "1_1") (pintype "passive"))
      (node (ref "U$6") (pin "13") (pinfunction "D3_13") (pintype "bidirectional"))
    )
    (net (code "26") (name "EP8") (class "Default")
      (node (ref "08") (pin "1") (pinfunction "1_1") (pintype "passive"))
      (node (ref "U$6") (pin "18") (pinfunction "D4_18") (pintype "bidirectional"))
    )
    (net (code "27") (name "EP9") (class "Default")
      (node (ref "13") (pin "1") (pinfunction "1_1") (pintype "passive"))
      (node (ref "U$12") (pin "3") (pinfunction "D1_3") (pintype "bidirectional"))
    )
    (net (code "28") (name "EP10") (class "Default")
      (node (ref "14") (pin "1") (pinfunction "1_1") (pintype "passive"))
      (node (ref "U$12") (pin "8") (pinfunction "D2_8") (pintype "bidirectional"))
    )
    (net (code "29") (name "EP11") (class "Default")
      (node (ref "09") (pin "1") (pinfunction "1_1") (pintype "passive"))
      (node (ref "U$12") (pin "13") (pinfunction "D3_13") (pintype "bidirectional"))
    )
    (net (code "30") (name "EP12") (class "Default")
      (node (ref "10") (pin "1") (pinfunction "1_1") (pintype "passive"))
      (node (ref "U$12") (pin "18") (pinfunction "D4_18") (pintype "bidirectional"))
    )
    (net (code "31") (name "EP13") (class "Default")
      (node (ref "12") (pin "1") (pinfunction "1_1") (pintype "passive"))
      (node (ref "U$5") (pin "3") (pinfunction "D1_3") (pintype "bidirectional"))
    )
    (net (code "32") (name "EP14") (class "Default")
      (node (ref "11") (pin "1") (pinfunction "1_1") (pintype "passive"))
      (node (ref "U$5") (pin "8") (pinfunction "D2_8") (pintype "bidirectional"))
    )
    (net (code "33") (name "EP15") (class "Default")
      (node (ref "15") (pin "1") (pinfunction "1_1") (pintype "passive"))
      (node (ref "U$5") (pin "13") (pinfunction "D3_13") (pintype "bidirectional"))
    )
    (net (code "34") (name "EP16") (class "Default")
      (node (ref "16") (pin "1") (pinfunction "1_1") (pintype "passive"))
      (node (ref "U$5") (pin "18") (pinfunction "D4_18") (pintype "bidirectional"))
    )
    (net (code "35") (name "EP17") (class "Default")
      (node (ref "29") (pin "1") (pinfunction "1_1") (pintype "passive"))
      (node (ref "U$3") (pin "3") (pinfunction "D1_3") (pintype "bidirectional"))
    )
    (net (code "36") (name "EP18") (class "Default")
      (node (ref "28") (pin "1") (pinfunction "1_1") (pintype "passive"))
      (node (ref "U$3") (pin "8") (pinfunction "D2_8") (pintype "bidirectional"))
    )
    (net (code "37") (name "EP19") (class "Default")
      (node (ref "25") (pin "1") (pinfunction "1_1") (pintype "passive"))
      (node (ref "U$3") (pin "13") (pinfunction "D3_13") (pintype "bidirectional"))
    )
    (net (code "38") (name "EP20") (class "Default")
      (node (ref "32") (pin "1") (pinfunction "1_1") (pintype "passive"))
      (node (ref "U$3") (pin "18") (pinfunction "D4_18") (pintype "bidirectional"))
    )
    (net (code "39") (name "EP21") (class "Default")
      (node (ref "19") (pin "1") (pinfunction "1_1") (pintype "passive"))
      (node (ref "U$10") (pin "3") (pinfunction "D1_3") (pintype "bidirectional"))
    )
    (net (code "40") (name "EP22") (class "Default")
      (node (ref "20") (pin "1") (pinfunction "1_1") (pintype "passive"))
      (node (ref "U$10") (pin "8") (pinfunction "D2_8") (pintype "bidirectional"))
    )
    (net (code "41") (name "EP23") (class "Default")
      (node (ref "23") (pin "1") (pinfunction "1_1") (pintype "passive"))
      (node (ref "U$10") (pin "13") (pinfunction "D3_13") (pintype "bidirectional"))
    )
    (net (code "42") (name "EP24") (class "Default")
      (node (ref "24") (pin "1") (pinfunction "1_1") (pintype "passive"))
      (node (ref "U$10") (pin "18") (pinfunction "D4_18") (pintype "bidirectional"))
    )
    (net (code "43") (name "EP25") (class "Default")
      (node (ref "22") (pin "1") (pinfunction "1_1") (pintype "passive"))
      (node (ref "U$4") (pin "3") (pinfunction "D1_3") (pintype "bidirectional"))
    )
    (net (code "44") (name "EP26") (class "Default")
      (node (ref "21") (pin "1") (pinfunction "1_1") (pintype "passive"))
      (node (ref "U$4") (pin "8") (pinfunction "D2_8") (pintype "bidirectional"))
    )
    (net (code "45") (name "EP27") (class "Default")
      (node (ref "17") (pin "1") (pinfunction "1_1") (pintype "passive"))
      (node (ref "U$4") (pin "13") (pinfunction "D3_13") (pintype "bidirectional"))
    )
    (net (code "46") (name "EP28") (class "Default")
      (node (ref "18") (pin "1") (pinfunction "1_1") (pintype "passive"))
      (node (ref "U$4") (pin "18") (pinfunction "D4_18") (pintype "bidirectional"))
    )
    (net (code "47") (name "EP29") (class "Default")
      (node (ref "30") (pin "1") (pinfunction "1_1") (pintype "passive"))
      (node (ref "U$11") (pin "3") (pinfunction "D1_3") (pintype "bidirectional"))
    )
    (net (code "48") (name "EP30") (class "Default")
      (node (ref "31") (pin "1") (pinfunction "1_1") (pintype "passive"))
      (node (ref "U$11") (pin "8") (pinfunction "D2_8") (pintype "bidirectional"))
    )
    (net (code "49") (name "EP31") (class "Default")
      (node (ref "26") (pin "1") (pinfunction "1_1") (pintype "passive"))
      (node (ref "U$11") (pin "13") (pinfunction "D3_13") (pintype "bidirectional"))
    )
    (net (code "50") (name "EP32") (class "Default")
      (node (ref "27") (pin "1") (pinfunction "1_1") (pintype "passive"))
      (node (ref "U$11") (pin "18") (pinfunction "D4_18") (pintype "bidirectional"))
    )
    (net (code "51") (name "GND") (class "Default")
      (node (ref "01") (pin "2") (pinfunction "2_2") (pintype "passive"))
      (node (ref "02") (pin "2") (pinfunction "2_2") (pintype "passive"))
      (node (ref "03") (pin "2") (pinfunction "2_2") (pintype "passive"))
      (node (ref "04") (pin "2") (pinfunction "2_2") (pintype "passive"))
      (node (ref "05") (pin "2") (pinfunction "2_2") (pintype "passive"))
      (node (ref "06") (pin "2") (pinfunction "2_2") (pintype "passive"))
      (node (ref "07") (pin "2") (pinfunction "2_2") (pintype "passive"))
      (node (ref "08") (pin "2") (pinfunction "2_2") (pintype "passive"))
      (node (ref "09") (pin "2") (pinfunction "2_2") (pintype "passive"))
      (node (ref "10") (pin "2") (pinfunction "2_2") (pintype "passive"))
      (node (ref "11") (pin "2") (pinfunction "2_2") (pintype "passive"))
      (node (ref "12") (pin "2") (pinfunction "2_2") (pintype "passive"))
      (node (ref "13") (pin "2") (pinfunction "2_2") (pintype "passive"))
      (node (ref "14") (pin "2") (pinfunction "2_2") (pintype "passive"))
      (node (ref "15") (pin "2") (pinfunction "2_2") (pintype "passive"))
      (node (ref "16") (pin "2") (pinfunction "2_2") (pintype "passive"))
      (node (ref "17") (pin "2") (pinfunction "2_2") (pintype "passive"))
      (node (ref "18") (pin "2") (pinfunction "2_2") (pintype "passive"))
      (node (ref "19") (pin "2") (pinfunction "2_2") (pintype "passive"))
      (node (ref "20") (pin "2") (pinfunction "2_2") (pintype "passive"))
      (node (ref "21") (pin "2") (pinfunction "2_2") (pintype "passive"))
      (node (ref "22") (pin "2") (pinfunction "2_2") (pintype "passive"))
      (node (ref "23") (pin "2") (pinfunction "2_2") (pintype "passive"))
      (node (ref "24") (pin "2") (pinfunction "2_2") (pintype "passive"))
      (node (ref "25") (pin "2") (pinfunction "2_2") (pintype "passive"))
      (node (ref "26") (pin "2") (pinfunction "2_2") (pintype "passive"))
      (node (ref "27") (pin "2") (pinfunction "2_2") (pintype "passive"))
      (node (ref "28") (pin "2") (pinfunction "2_2") (pintype "passive"))
      (node (ref "29") (pin "2") (pinfunction "2_2") (pintype "passive"))
      (node (ref "30") (pin "2") (pinfunction "2_2") (pintype "passive"))
      (node (ref "31") (pin "2") (pinfunction "2_2") (pintype "passive"))
      (node (ref "32") (pin "2") (pinfunction "2_2") (pintype "passive"))
      (node (ref "C1") (pin "1") (pinfunction "1_1") (pintype "passive"))
      (node (ref "C10") (pin "2") (pinfunction "2_2") (pintype "passive"))
      (node (ref "C11") (pin "1") (pinfunction "1_1") (pintype "passive"))
      (node (ref "C12") (pin "1") (pinfunction "1_1") (pintype "passive"))
      (node (ref "C13") (pin "1") (pinfunction "1_1") (pintype "passive"))
      (node (ref "C14") (pin "1") (pinfunction "1_1") (pintype "passive"))
      (node (ref "C2") (pin "2") (pinfunction "2_2") (pintype "passive"))
      (node (ref "C3") (pin "2") (pinfunction "2_2") (pintype "passive"))
      (node (ref "C4") (pin "1") (pinfunction "1_1") (pintype "passive"))
      (node (ref "C5") (pin "2") (pinfunction "2_2") (pintype "passive"))
      (node (ref "C6") (pin "2") (pinfunction "2_2") (pintype "passive"))
      (node (ref "C7") (pin "1") (pinfunction "1_1") (pintype "passive"))
      (node (ref "C8") (pin "1") (pinfunction "1_1") (pintype "passive"))
      (node (ref "C9") (pin "2") (pinfunction "2_2") (pintype "passive"))
      (node (ref "D2]") (pin "C") (pinfunction "C_C") (pintype "passive"))
      (node (ref "D3") (pin "C") (pinfunction "C_C") (pintype "passive"))
      (node (ref "D4") (pin "C") (pinfunction "C_C") (pintype "passive"))
      (node (ref "D5") (pin "C") (pinfunction "C_C") (pintype "passive"))
      (node (ref "GD") (pin "1") (pinfunction "1_1") (pintype "passive"))
      (node (ref "GND") (pin "1") (pinfunction "1_1") (pintype "passive"))
      (node (ref "IC1") (pin "5") (pinfunction "GND_5") (pintype "bidirectional"))
      (node (ref "IC2") (pin "2") (pinfunction "GND_2") (pintype "bidirectional"))
      (node (ref "JP2") (pin "3") (pinfunction "3_3") (pintype "passive"))
      (node (ref "Q1") (pin "2") (pinfunction "S_2") (pintype "passive"))
      (node (ref "R10") (pin "2") (pinfunction "2_2") (pintype "passive"))
      (node (ref "R24") (pin "2") (pinfunction "2_2") (pintype "passive"))
      (node (ref "R5") (pin "1") (pinfunction "1_1") (pintype "passive"))
      (node (ref "R6") (pin "1") (pinfunction "1_1") (pintype "passive"))
      (node (ref "S1") (pin "3") (pinfunction "2_3") (pintype "passive"))
      (node (ref "U$1") (pin "GND") (pinfunction "GND_GND") (pintype "bidirectional"))
      (node (ref "U$1") (pin "P$6") (pinfunction "MTN1_P$6") (pintype "bidirectional"))
      (node (ref "U$1") (pin "P$7") (pinfunction "MTN2_P$7") (pintype "bidirectional"))
      (node (ref "U$1") (pin "P$8") (pinfunction "MTN3_P$8") (pintype "bidirectional"))
      (node (ref "U$1") (pin "P$9") (pinfunction "MTN4_P$9") (pintype "bidirectional"))
      (node (ref "U$10") (pin "6") (pinfunction "GND_6") (pintype "bidirectional"))
      (node (ref "U$11") (pin "6") (pinfunction "GND_6") (pintype "bidirectional"))
      (node (ref "U$12") (pin "6") (pinfunction "GND_6") (pintype "bidirectional"))
      (node (ref "U$13") (pin "6") (pinfunction "GND_6") (pintype "bidirectional"))
      (node (ref "U$2") (pin "P$2") (pinfunction "-VIN_P$2") (pintype "bidirectional"))
      (node (ref "U$2") (pin "P$5") (pinfunction "COM_P$5") (pintype "bidirectional"))
      (node (ref "U$3") (pin "6") (pinfunction "GND_6") (pintype "bidirectional"))
      (node (ref "U$4") (pin "6") (pinfunction "GND_6") (pintype "bidirectional"))
      (node (ref "U$5") (pin "6") (pinfunction "GND_6") (pintype "bidirectional"))
      (node (ref "U$6") (pin "6") (pinfunction "GND_6") (pintype "bidirectional"))
      (node (ref "U$7") (pin "15") (pinfunction "GND_15") (pintype "bidirectional"))
      (node (ref "U$7") (pin "23") (pinfunction "GND2_23") (pintype "bidirectional"))
      (node (ref "U$7") (pin "35") (pinfunction "GND3_35") (pintype "bidirectional"))
      (node (ref "U$7") (pin "43") (pinfunction "GND4_43") (pintype "bidirectional"))
      (node (ref "U$7") (pin "5") (pinfunction "UGND_5") (pintype "bidirectional"))
      (node (ref "U$8") (pin "1") (pinfunction "A0_1") (pintype "bidirectional"))
      (node (ref "U$8") (pin "14") (pinfunction "VSS_14") (pintype "bidirectional"))
      (node (ref "U$8") (pin "2") (pinfunction "A1_2") (pintype "bidirectional"))
      (node (ref "U$8") (pin "23") (pinfunction "OE_23") (pintype "bidirectional"))
      (node (ref "U$8") (pin "24") (pinfunction "A5_24") (pintype "bidirectional"))
      (node (ref "U$8") (pin "3") (pinfunction "A2_3") (pintype "bidirectional"))
      (node (ref "U$8") (pin "4") (pinfunction "A3_4") (pintype "bidirectional"))
      (node (ref "U$9") (pin "1") (pinfunction "A0_1") (pintype "bidirectional"))
      (node (ref "U$9") (pin "14") (pinfunction "VSS_14") (pintype "bidirectional"))
      (node (ref "U$9") (pin "2") (pinfunction "A1_2") (pintype "bidirectional"))
      (node (ref "U$9") (pin "23") (pinfunction "OE_23") (pintype "bidirectional"))
      (node (ref "U$9") (pin "24") (pinfunction "A5_24") (pintype "bidirectional"))
      (node (ref "U$9") (pin "3") (pinfunction "A2_3") (pintype "bidirectional"))
      (node (ref "U$9") (pin "5") (pinfunction "A4_5") (pintype "bidirectional"))
      (node (ref "U1") (pin "10") (pinfunction "GND_10") (pintype "bidirectional"))
    )
    (net (code "52") (name "IN3-1") (class "Default")
      (node (ref "U$3") (pin "1") (pinfunction "IN1_1") (pintype "bidirectional"))
      (node (ref "U$9") (pin "10") (pinfunction "LED4_10") (pintype "bidirectional"))
    )
    (net (code "53") (name "IN3-2") (class "Default")
      (node (ref "U$3") (pin "10") (pinfunction "IN2_10") (pintype "bidirectional"))
      (node (ref "U$9") (pin "9") (pinfunction "LED3_9") (pintype "bidirectional"))
    )
    (net (code "54") (name "IN3-3") (class "Default")
      (node (ref "U$3") (pin "11") (pinfunction "IN3_11") (pintype "bidirectional"))
      (node (ref "U$9") (pin "6") (pinfunction "LED0_6") (pintype "bidirectional"))
    )
    (net (code "55") (name "IN3-4") (class "Default")
      (node (ref "U$3") (pin "20") (pinfunction "IN4_20") (pintype "bidirectional"))
      (node (ref "U$9") (pin "11") (pinfunction "LED5_11") (pintype "bidirectional"))
    )
    (net (code "56") (name "IN4-1") (class "Default")
      (node (ref "U$4") (pin "1") (pinfunction "IN1_1") (pintype "bidirectional"))
      (node (ref "U$9") (pin "18") (pinfunction "LED11_18") (pintype "bidirectional"))
    )
    (net (code "57") (name "IN4-2") (class "Default")
      (node (ref "U$4") (pin "10") (pinfunction "IN2_10") (pintype "bidirectional"))
      (node (ref "U$9") (pin "19") (pinfunction "LED12_19") (pintype "bidirectional"))
    )
    (net (code "58") (name "IN4-3") (class "Default")
      (node (ref "U$4") (pin "11") (pinfunction "IN3_11") (pintype "bidirectional"))
      (node (ref "U$9") (pin "20") (pinfunction "LED13_20") (pintype "bidirectional"))
    )
    (net (code "59") (name "IN4-4") (class "Default")
      (node (ref "U$4") (pin "20") (pinfunction "IN4_20") (pintype "bidirectional"))
      (node (ref "U$9") (pin "15") (pinfunction "LED8_15") (pintype "bidirectional"))
    )
    (net (code "60") (name "IN5-1") (class "Default")
      (node (ref "U$5") (pin "1") (pinfunction "IN1_1") (pintype "bidirectional"))
      (node (ref "U$8") (pin "8") (pinfunction "LED2_8") (pintype "bidirectional"))
    )
    (net (code "61") (name "IN5-2") (class "Default")
      (node (ref "U$5") (pin "10") (pinfunction "IN2_10") (pintype "bidirectional"))
      (node (ref "U$8") (pin "10") (pinfunction "LED4_10") (pintype "bidirectional"))
    )
    (net (code "62") (name "IN5-3") (class "Default")
      (node (ref "U$5") (pin "11") (pinfunction "IN3_11") (pintype "bidirectional"))
      (node (ref "U$8") (pin "12") (pinfunction "LED6_12") (pintype "bidirectional"))
    )
    (net (code "63") (name "IN5-4") (class "Default")
      (node (ref "U$5") (pin "20") (pinfunction "IN4_20") (pintype "bidirectional"))
      (node (ref "U$8") (pin "6") (pinfunction "LED0_6") (pintype "bidirectional"))
    )
    (net (code "64") (name "IN6-1") (class "Default")
      (node (ref "U$6") (pin "1") (pinfunction "IN1_1") (pintype "bidirectional"))
      (node (ref "U$8") (pin "22") (pinfunction "LED15_22") (pintype "bidirectional"))
    )
    (net (code "65") (name "IN6-2") (class "Default")
      (node (ref "U$6") (pin "10") (pinfunction "IN2_10") (pintype "bidirectional"))
      (node (ref "U$8") (pin "18") (pinfunction "LED11_18") (pintype "bidirectional"))
    )
    (net (code "66") (name "IN6-3") (class "Default")
      (node (ref "U$6") (pin "11") (pinfunction "IN3_11") (pintype "bidirectional"))
      (node (ref "U$8") (pin "15") (pinfunction "LED8_15") (pintype "bidirectional"))
    )
    (net (code "67") (name "IN6-4") (class "Default")
      (node (ref "U$6") (pin "20") (pinfunction "IN4_20") (pintype "bidirectional"))
      (node (ref "U$8") (pin "21") (pinfunction "LED14_21") (pintype "bidirectional"))
    )
    (net (code "68") (name "IN10-1") (class "Default")
      (node (ref "U$10") (pin "1") (pinfunction "IN1_1") (pintype "bidirectional"))
      (node (ref "U$9") (pin "22") (pinfunction "LED15_22") (pintype "bidirectional"))
    )
    (net (code "69") (name "IN10-2") (class "Default")
      (node (ref "U$10") (pin "10") (pinfunction "IN2_10") (pintype "bidirectional"))
      (node (ref "U$9") (pin "21") (pinfunction "LED14_21") (pintype "bidirectional"))
    )
    (net (code "70") (name "IN10-3") (class "Default")
      (node (ref "U$10") (pin "11") (pinfunction "IN3_11") (pintype "bidirectional"))
      (node (ref "U$9") (pin "17") (pinfunction "LED10_17") (pintype "bidirectional"))
    )
    (net (code "71") (name "IN10-4") (class "Default")
      (node (ref "U$10") (pin "20") (pinfunction "IN4_20") (pintype "bidirectional"))
      (node (ref "U$9") (pin "16") (pinfunction "LED9_16") (pintype "bidirectional"))
    )
    (net (code "72") (name "IN11-1") (class "Default")
      (node (ref "U$11") (pin "1") (pinfunction "IN1_1") (pintype "bidirectional"))
      (node (ref "U$9") (pin "12") (pinfunction "LED6_12") (pintype "bidirectional"))
    )
    (net (code "73") (name "IN11-2") (class "Default")
      (node (ref "U$11") (pin "10") (pinfunction "IN2_10") (pintype "bidirectional"))
      (node (ref "U$9") (pin "13") (pinfunction "LED7_13") (pintype "bidirectional"))
    )
    (net (code "74") (name "IN11-3") (class "Default")
      (node (ref "U$11") (pin "11") (pinfunction "IN3_11") (pintype "bidirectional"))
      (node (ref "U$9") (pin "7") (pinfunction "LED1_7") (pintype "bidirectional"))
    )
    (net (code "75") (name "IN11-4") (class "Default")
      (node (ref "U$11") (pin "20") (pinfunction "IN4_20") (pintype "bidirectional"))
      (node (ref "U$9") (pin "8") (pinfunction "LED2_8") (pintype "bidirectional"))
    )
    (net (code "76") (name "IN12-1") (class "Default")
      (node (ref "U$12") (pin "1") (pinfunction "IN1_1") (pintype "bidirectional"))
      (node (ref "U$8") (pin "9") (pinfunction "LED3_9") (pintype "bidirectional"))
    )
    (net (code "77") (name "IN12-2") (class "Default")
      (node (ref "U$12") (pin "10") (pinfunction "IN2_10") (pintype "bidirectional"))
      (node (ref "U$8") (pin "7") (pinfunction "LED1_7") (pintype "bidirectional"))
    )
    (net (code "78") (name "IN12-3") (class "Default")
      (node (ref "U$12") (pin "11") (pinfunction "IN3_11") (pintype "bidirectional"))
      (node (ref "U$8") (pin "13") (pinfunction "LED7_13") (pintype "bidirectional"))
    )
    (net (code "79") (name "IN12-4") (class "Default")
      (node (ref "U$12") (pin "20") (pinfunction "IN4_20") (pintype "bidirectional"))
      (node (ref "U$8") (pin "11") (pinfunction "LED5_11") (pintype "bidirectional"))
    )
    (net (code "80") (name "IN13-1") (class "Default")
      (node (ref "U$13") (pin "1") (pinfunction "IN1_1") (pintype "bidirectional"))
      (node (ref "U$8") (pin "16") (pinfunction "LED9_16") (pintype "bidirectional"))
    )
    (net (code "81") (name "IN13-2") (class "Default")
      (node (ref "U$13") (pin "10") (pinfunction "IN2_10") (pintype "bidirectional"))
      (node (ref "U$8") (pin "17") (pinfunction "LED10_17") (pintype "bidirectional"))
    )
    (net (code "82") (name "IN13-3") (class "Default")
      (node (ref "U$13") (pin "11") (pinfunction "IN3_11") (pintype "bidirectional"))
      (node (ref "U$8") (pin "19") (pinfunction "LED12_19") (pintype "bidirectional"))
    )
    (net (code "83") (name "IN13-4") (class "Default")
      (node (ref "U$13") (pin "20") (pinfunction "IN4_20") (pintype "bidirectional"))
      (node (ref "U$8") (pin "20") (pinfunction "LED13_20") (pintype "bidirectional"))
    )
    (net (code "84") (name "IO8") (class "Default")
      (node (ref "JP3") (pin "3") (pinfunction "3_3") (pintype "passive"))
      (node (ref "U$7") (pin "28") (pinfunction "(PCINT4/ADC11)PB4_28") (pintype "bidirectional"))
    )
    (net (code "85") (name "IO9") (class "Default")
      (node (ref "JP3") (pin "4") (pinfunction "4_4") (pintype "passive"))
      (node (ref "U$7") (pin "29") (pinfunction "(PCINT5/OC1A/OC4B/ADC12)PB5_29") (pintype "bidirectional"))
    )
    (net (code "86") (name "IO10") (class "Default")
      (node (ref "JP3") (pin "5") (pinfunction "5_5") (pintype "passive"))
      (node (ref "U$7") (pin "30") (pinfunction "(PCINT6/OC1B/OC4B/ADC13)PB6_30") (pintype "bidirectional"))
    )
    (net (code "87") (name "IO11") (class "Default")
      (node (ref "JP2") (pin "6") (pinfunction "6_6") (pintype "passive"))
      (node (ref "U$7") (pin "12") (pinfunction "(PCINT7/OC0A/OC1C/RTS)PB7_12") (pintype "bidirectional"))
    )
    (net (code "88") (name "IO12") (class "Default")
      (node (ref "JP3") (pin "1") (pinfunction "1_1") (pintype "passive"))
      (node (ref "U$7") (pin "26") (pinfunction "(T1/OC4D/ADC9)PD6_26") (pintype "bidirectional"))
    )
    (net (code "89") (name "MISO") (class "Default")
      (node (ref "JP2") (pin "8") (pinfunction "8_8") (pintype "passive"))
      (node (ref "U$7") (pin "11") (pinfunction "(PDO/PCINT3/MISO)PB3_11") (pintype "bidirectional"))
    )
    (net (code "90") (name "MOSI") (class "Default")
      (node (ref "JP2") (pin "9") (pinfunction "9_9") (pintype "passive"))
      (node (ref "U$7") (pin "10") (pinfunction "(PDI/PCINT2/MOSI)PB2_10") (pintype "bidirectional"))
    )
    (net (code "91") (name "Net-(C10-Pad1)") (class "Default")
      (node (ref "C10") (pin "1") (pinfunction "1_1") (pintype "passive"))
      (node (ref "C9") (pin "1") (pinfunction "1_1") (pintype "passive"))
      (node (ref "R1") (pin "2") (pinfunction "2_2") (pintype "passive"))
      (node (ref "U$1") (pin "VBUS") (pinfunction "VBUS_VBUS") (pintype "bidirectional"))
    )
    (net (code "92") (name "Net-(D1-A)") (class "Default")
      (node (ref "D1") (pin "1") (pinfunction "A_1") (pintype "passive"))
      (node (ref "R9") (pin "2") (pinfunction "2_2") (pintype "passive"))
      (node (ref "S1") (pin "1") (pinfunction "1_1") (pintype "passive"))
      (node (ref "U$7") (pin "13") (pinfunction "RESET_13") (pintype "bidirectional"))
    )
    (net (code "93") (name "Net-(D2]-PadA)") (class "Default")
      (node (ref "D2]") (pin "A") (pinfunction "A_A") (pintype "passive"))
      (node (ref "R14") (pin "2") (pinfunction "2_2") (pintype "passive"))
    )
    (net (code "94") (name "Net-(D3-PadA)") (class "Default")
      (node (ref "D3") (pin "A") (pinfunction "A_A") (pintype "passive"))
      (node (ref "R12") (pin "1") (pinfunction "1_1") (pintype "passive"))
    )
    (net (code "95") (name "Net-(D4-PadA)") (class "Default")
      (node (ref "D4") (pin "A") (pinfunction "A_A") (pintype "passive"))
      (node (ref "R11") (pin "2") (pinfunction "2_2") (pintype "passive"))
    )
    (net (code "96") (name "Net-(D5-PadA)") (class "Default")
      (node (ref "D5") (pin "A") (pinfunction "A_A") (pintype "passive"))
      (node (ref "R13") (pin "2") (pinfunction "2_2") (pintype "passive"))
    )
    (net (code "97") (name "Net-(IC2-XEN{slash}EN)") (class "Default")
      (node (ref "IC2") (pin "3") (pinfunction "XEN/EN_3") (pintype "bidirectional"))
      (node (ref "R21") (pin "1") (pinfunction "1_1") (pintype "passive"))
    )
    (net (code "98") (name "Net-(Q1-D)") (class "Default")
      (node (ref "Q1") (pin "3") (pinfunction "D_3") (pintype "passive"))
      (node (ref "Q2") (pin "1") (pinfunction "G_1") (pintype "passive"))
      (node (ref "R27") (pin "1") (pinfunction "1_1") (pintype "passive"))
    )
    (net (code "99") (name "Net-(Q1-G)") (class "Default")
      (node (ref "Q1") (pin "1") (pinfunction "G_1") (pintype "passive"))
      (node (ref "R28") (pin "1") (pinfunction "1_1") (pintype "passive"))
    )
    (net (code "100") (name "Net-(R7-Pad2)") (class "Default")
      (node (ref "R7") (pin "2") (pinfunction "2_2") (pintype "passive"))
      (node (ref "U$1") (pin "D-") (pinfunction "D-_D-") (pintype "bidirectional"))
    )
    (net (code "101") (name "Net-(R8-Pad2)") (class "Default")
      (node (ref "R8") (pin "2") (pinfunction "2_2") (pintype "passive"))
      (node (ref "U$1") (pin "D+") (pinfunction "D+_D+") (pintype "bidirectional"))
    )
    (net (code "102") (name "Net-(U$2-+VIN)") (class "Default")
      (node (ref "C2") (pin "1") (pinfunction "1_1") (pintype "passive"))
      (node (ref "R2") (pin "2") (pinfunction "2_2") (pintype "passive"))
      (node (ref "U$2") (pin "P$1") (pinfunction "+VIN_P$1") (pintype "bidirectional"))
    )
    (net (code "103") (name "Net-(U$2-+VOUT)") (class "Default")
      (node (ref "R3") (pin "1") (pinfunction "1_1") (pintype "passive"))
      (node (ref "R5") (pin "2") (pinfunction "2_2") (pintype "passive"))
      (node (ref "U$2") (pin "P$6") (pinfunction "+VOUT_P$6") (pintype "bidirectional"))
    )
    (net (code "104") (name "Net-(U$2--VOUT)") (class "Default")
      (node (ref "R4") (pin "2") (pinfunction "2_2") (pintype "passive"))
      (node (ref "R6") (pin "2") (pinfunction "2_2") (pintype "passive"))
      (node (ref "U$2") (pin "P$4") (pinfunction "-VOUT_P$4") (pintype "bidirectional"))
    )
    (net (code "105") (name "Net-(U$7-(HWB)PE2)") (class "Default")
      (node (ref "R10") (pin "1") (pinfunction "1_1") (pintype "passive"))
      (node (ref "U$7") (pin "33") (pinfunction "(HWB)PE2_33") (pintype "bidirectional"))
    )
    (net (code "106") (name "Net-(U$7-(ICP3{slash}CLK0{slash}OC4A)PC7)") (class "Default")
      (node (ref "R14") (pin "1") (pinfunction "1_1") (pintype "passive"))
      (node (ref "U$7") (pin "32") (pinfunction "(ICP3/CLK0/OC4A)PC7_32") (pintype "bidirectional"))
    )
    (net (code "107") (name "Net-(U$7-(XCK1{slash}CTS)PD5)") (class "Default")
      (node (ref "R13") (pin "1") (pinfunction "1_1") (pintype "passive"))
      (node (ref "U$7") (pin "22") (pinfunction "(XCK1/CTS)PD5_22") (pintype "bidirectional"))
    )
    (net (code "108") (name "Net-(U$7-AREF)") (class "Default")
      (node (ref "C8") (pin "2") (pinfunction "2_2") (pintype "passive"))
      (node (ref "U$7") (pin "42") (pinfunction "AREF_42") (pintype "bidirectional"))
    )
    (net (code "109") (name "Net-(U$7-UCAP)") (class "Default")
      (node (ref "C1") (pin "2") (pinfunction "2_2") (pintype "passive"))
      (node (ref "U$7") (pin "6") (pinfunction "UCAP_6") (pintype "bidirectional"))
    )
    (net (code "110") (name "Net-(U$7-XTAL1)") (class "Default")
      (node (ref "C4") (pin "2") (pinfunction "2_2") (pintype "passive"))
      (node (ref "U$7") (pin "17") (pinfunction "XTAL1_17") (pintype "bidirectional"))
      (node (ref "Y1") (pin "P$3") (pinfunction "2_P$3") (pintype "passive"))
    )
    (net (code "111") (name "Net-(U$7-XTAL2)") (class "Default")
      (node (ref "C3") (pin "1") (pinfunction "1_1") (pintype "passive"))
      (node (ref "U$7") (pin "16") (pinfunction "XTAL2_16") (pintype "bidirectional"))
      (node (ref "Y1") (pin "P$1") (pinfunction "1_P$1") (pintype "passive"))
    )
    (net (code "112") (name "Net-(U$14-P$1)") (class "Default")
      (node (ref "U$14") (pin "1") (pinfunction "P$1_1") (pintype "bidirectional"))
      (node (ref "U$7") (pin "44") (pinfunction "AVCC2_44") (pintype "bidirectional"))
    )
    (net (code "113") (name "Net-(U1-RXD)") (class "Default")
      (node (ref "R23") (pin "2") (pinfunction "2_2") (pintype "passive"))
      (node (ref "R24") (pin "1") (pinfunction "1_1") (pintype "passive"))
      (node (ref "U1") (pin "3") (pinfunction "RXD_3") (pintype "output"))
    )
    (net (code "114") (name "Net-(U1-TXD)") (class "Default")
      (node (ref "R22") (pin "1") (pinfunction "1_1") (pintype "passive"))
      (node (ref "U1") (pin "2") (pinfunction "TXD_2") (pintype "input"))
    )
    (net (code "115") (name "RD+") (class "Default")
      (node (ref "R8") (pin "1") (pinfunction "1_1") (pintype "passive"))
      (node (ref "U$7") (pin "4") (pinfunction "D+_4") (pintype "bidirectional"))
    )
    (net (code "116") (name "RD-") (class "Default")
      (node (ref "R7") (pin "1") (pinfunction "1_1") (pintype "passive"))
      (node (ref "U$7") (pin "3") (pinfunction "D-_3") (pintype "bidirectional"))
    )
    (net (code "117") (name "RXLED{slash}SS") (class "Default")
      (node (ref "JP2") (pin "11") (pinfunction "11_11") (pintype "passive"))
      (node (ref "R11") (pin "1") (pinfunction "1_1") (pintype "passive"))
      (node (ref "U$7") (pin "8") (pinfunction "(SS/PCINT0)PB0_8") (pintype "bidirectional"))
    )
    (net (code "118") (name "SCK") (class "Default")
      (node (ref "JP2") (pin "10") (pinfunction "10_10") (pintype "passive"))
      (node (ref "U$7") (pin "9") (pinfunction "(PCINT1/SCLK)PB1_9") (pintype "bidirectional"))
    )
    (net (code "119") (name "SCL") (class "Default")
      (node (ref "R19") (pin "1") (pinfunction "1_1") (pintype "passive"))
      (node (ref "U$7") (pin "18") (pinfunction "(OSC0B/SCL/INT0)PD0_18") (pintype "bidirectional"))
      (node (ref "U$8") (pin "26") (pinfunction "SCL_26") (pintype "bidirectional"))
      (node (ref "U$9") (pin "26") (pinfunction "SCL_26") (pintype "bidirectional"))
    )
    (net (code "120") (name "SDA") (class "Default")
      (node (ref "R20") (pin "1") (pinfunction "1_1") (pintype "passive"))
      (node (ref "U$7") (pin "19") (pinfunction "(SDA/INT1)PD1_19") (pintype "bidirectional"))
      (node (ref "U$8") (pin "27") (pinfunction "SDA_27") (pintype "bidirectional"))
      (node (ref "U$9") (pin "27") (pinfunction "SDA_27") (pintype "bidirectional"))
    )
    (net (code "121") (name "VPP") (class "Default")
      (node (ref "C11") (pin "2") (pinfunction "2_2") (pintype "passive"))
      (node (ref "C12") (pin "2") (pinfunction "2_2") (pintype "passive"))
      (node (ref "Q2") (pin "3") (pinfunction "D_3") (pintype "passive"))
      (node (ref "R15") (pin "1") (pinfunction "1_1") (pintype "passive"))
      (node (ref "R16") (pin "1") (pinfunction "1_1") (pintype "passive"))
      (node (ref "U$8") (pin "25") (pinfunction "A6_25") (pintype "bidirectional"))
      (node (ref "U$8") (pin "28") (pinfunction "VDD_28") (pintype "bidirectional"))
      (node (ref "U$8") (pin "5") (pinfunction "A4_5") (pintype "bidirectional"))
      (node (ref "U$9") (pin "25") (pinfunction "A6_25") (pintype "bidirectional"))
      (node (ref "U$9") (pin "28") (pinfunction "VDD_28") (pintype "bidirectional"))
      (node (ref "U$9") (pin "4") (pinfunction "A3_4") (pintype "bidirectional"))
    )
    (net (code "122") (name "unconnected-(IC1-D3-Pad10)") (class "Default")
      (node (ref "IC1") (pin "10") (pinfunction "D3_10") (pintype "bidirectional"))
    )
    (net (code "123") (name "unconnected-(IC1-D4-Pad7)") (class "Default")
      (node (ref "IC1") (pin "7") (pinfunction "D4_7") (pintype "bidirectional"))
    )
    (net (code "124") (name "unconnected-(IC1-IN3-Pad9)") (class "Default")
      (node (ref "IC1") (pin "9") (pinfunction "IN3_9") (pintype "bidirectional"))
    )
    (net (code "125") (name "unconnected-(IC1-IN4-Pad8)") (class "Default")
      (node (ref "IC1") (pin "8") (pinfunction "IN4_8") (pintype "bidirectional"))
    )
    (net (code "126") (name "unconnected-(IC1-S3-Pad11)") (class "Default")
      (node (ref "IC1") (pin "11") (pinfunction "S3_11") (pintype "bidirectional"))
    )
    (net (code "127") (name "unconnected-(IC1-S4-Pad6)") (class "Default")
      (node (ref "IC1") (pin "6") (pinfunction "S4_6") (pintype "bidirectional"))
    )
    (net (code "128") (name "unconnected-(IC2-NC-Pad4)") (class "Default")
      (node (ref "IC2") (pin "4") (pinfunction "NC_4") (pintype "no_connect"))
    )
    (net (code "129") (name "unconnected-(JP2-Pad2)") (class "Default")
      (node (ref "JP2") (pin "2") (pinfunction "2_2") (pintype "passive"))
    )
    (net (code "130") (name "unconnected-(U$1-PadID)") (class "Default")
      (node (ref "U$1") (pin "ID") (pinfunction "ID_ID") (pintype "bidirectional"))
    )
    (net (code "131") (name "unconnected-(U$3-NC-Pad15)") (class "Default")
      (node (ref "U$3") (pin "15") (pinfunction "NC_15") (pintype "no_connect"))
    )
    (net (code "132") (name "unconnected-(U$4-NC-Pad15)") (class "Default")
      (node (ref "U$4") (pin "15") (pinfunction "NC_15") (pintype "no_connect"))
    )
    (net (code "133") (name "unconnected-(U$5-NC-Pad15)") (class "Default")
      (node (ref "U$5") (pin "15") (pinfunction "NC_15") (pintype "no_connect"))
    )
    (net (code "134") (name "unconnected-(U$6-NC-Pad15)") (class "Default")
      (node (ref "U$6") (pin "15") (pinfunction "NC_15") (pintype "no_connect"))
    )
    (net (code "135") (name "unconnected-(U$10-NC-Pad15)") (class "Default")
      (node (ref "U$10") (pin "15") (pinfunction "NC_15") (pintype "no_connect"))
    )
    (net (code "136") (name "unconnected-(U$11-NC-Pad15)") (class "Default")
      (node (ref "U$11") (pin "15") (pinfunction "NC_15") (pintype "no_connect"))
    )
    (net (code "137") (name "unconnected-(U$12-NC-Pad15)") (class "Default")
      (node (ref "U$12") (pin "15") (pinfunction "NC_15") (pintype "no_connect"))
    )
    (net (code "138") (name "unconnected-(U$13-NC-Pad15)") (class "Default")
      (node (ref "U$13") (pin "15") (pinfunction "NC_15") (pintype "no_connect"))
    )
    (net (code "139") (name "unconnected-(U1-AIO0-Pad19)") (class "Default")
      (node (ref "U1") (pin "19") (pinfunction "AIO0_19") (pintype "bidirectional"))
    )
    (net (code "140") (name "unconnected-(U1-AIO1-Pad20)") (class "Default")
      (node (ref "U1") (pin "20") (pinfunction "AIO1_20") (pintype "bidirectional"))
    )
    (net (code "141") (name "unconnected-(U1-CTS-Pad16)") (class "Default")
      (node (ref "U1") (pin "16") (pinfunction "CTS_16") (pintype "bidirectional"))
    )
    (net (code "142") (name "unconnected-(U1-GPIIO7-Pad18)") (class "Default")
      (node (ref "U1") (pin "18") (pinfunction "GPIIO7_18") (pintype "bidirectional"))
    )
    (net (code "143") (name "unconnected-(U1-GPIO2-Pad13)") (class "Default")
      (node (ref "U1") (pin "13") (pinfunction "GPIO2_13") (pintype "bidirectional"))
    )
    (net (code "144") (name "unconnected-(U1-GPIO3-Pad17)") (class "Default")
      (node (ref "U1") (pin "17") (pinfunction "GPIO3_17") (pintype "bidirectional"))
    )
    (net (code "145") (name "unconnected-(U1-GPIO4-Pad8)") (class "Default")
      (node (ref "U1") (pin "8") (pinfunction "GPIO4_8") (pintype "bidirectional"))
    )
    (net (code "146") (name "unconnected-(U1-GPIO5-Pad15)") (class "Default")
      (node (ref "U1") (pin "15") (pinfunction "GPIO5_15") (pintype "bidirectional"))
    )
    (net (code "147") (name "unconnected-(U1-GPIO6-Pad6)") (class "Default")
      (node (ref "U1") (pin "6") (pinfunction "GPIO6_6") (pintype "bidirectional"))
    )
    (net (code "148") (name "unconnected-(U1-GPIO7-Pad4)") (class "Default")
      (node (ref "U1") (pin "4") (pinfunction "GPIO7_4") (pintype "bidirectional"))
    )
    (net (code "149") (name "unconnected-(U1-GPIO8-Pad11)") (class "Default")
      (node (ref "U1") (pin "11") (pinfunction "GPIO8_11") (pintype "bidirectional"))
    )
    (net (code "150") (name "unconnected-(U1-GPIO9-Pad7)") (class "Default")
      (node (ref "U1") (pin "7") (pinfunction "GPIO9_7") (pintype "bidirectional"))
    )
    (net (code "151") (name "unconnected-(U1-GPIO11-Pad9)") (class "Default")
      (node (ref "U1") (pin "9") (pinfunction "GPIO11_9") (pintype "bidirectional"))
    )
    (net (code "152") (name "unconnected-(U1-NC-Pad14)") (class "Default")
      (node (ref "U1") (pin "14") (pinfunction "NC_14") (pintype "no_connect"))
    )
    (net (code "153") (name "unconnected-(U1-RESET_N-Pad5)") (class "Default")
      (node (ref "U1") (pin "5") (pinfunction "RESET_N_5") (pintype "bidirectional"))
    )
    (net (code "154") (name "unconnected-(U1-RTS-Pad12)") (class "Default")
      (node (ref "U1") (pin "12") (pinfunction "RTS_12") (pintype "input"))
    )
  )
)
